# sla2216-conn-mso.net
KiCad netlist of a schematic drawn in Altium Designer
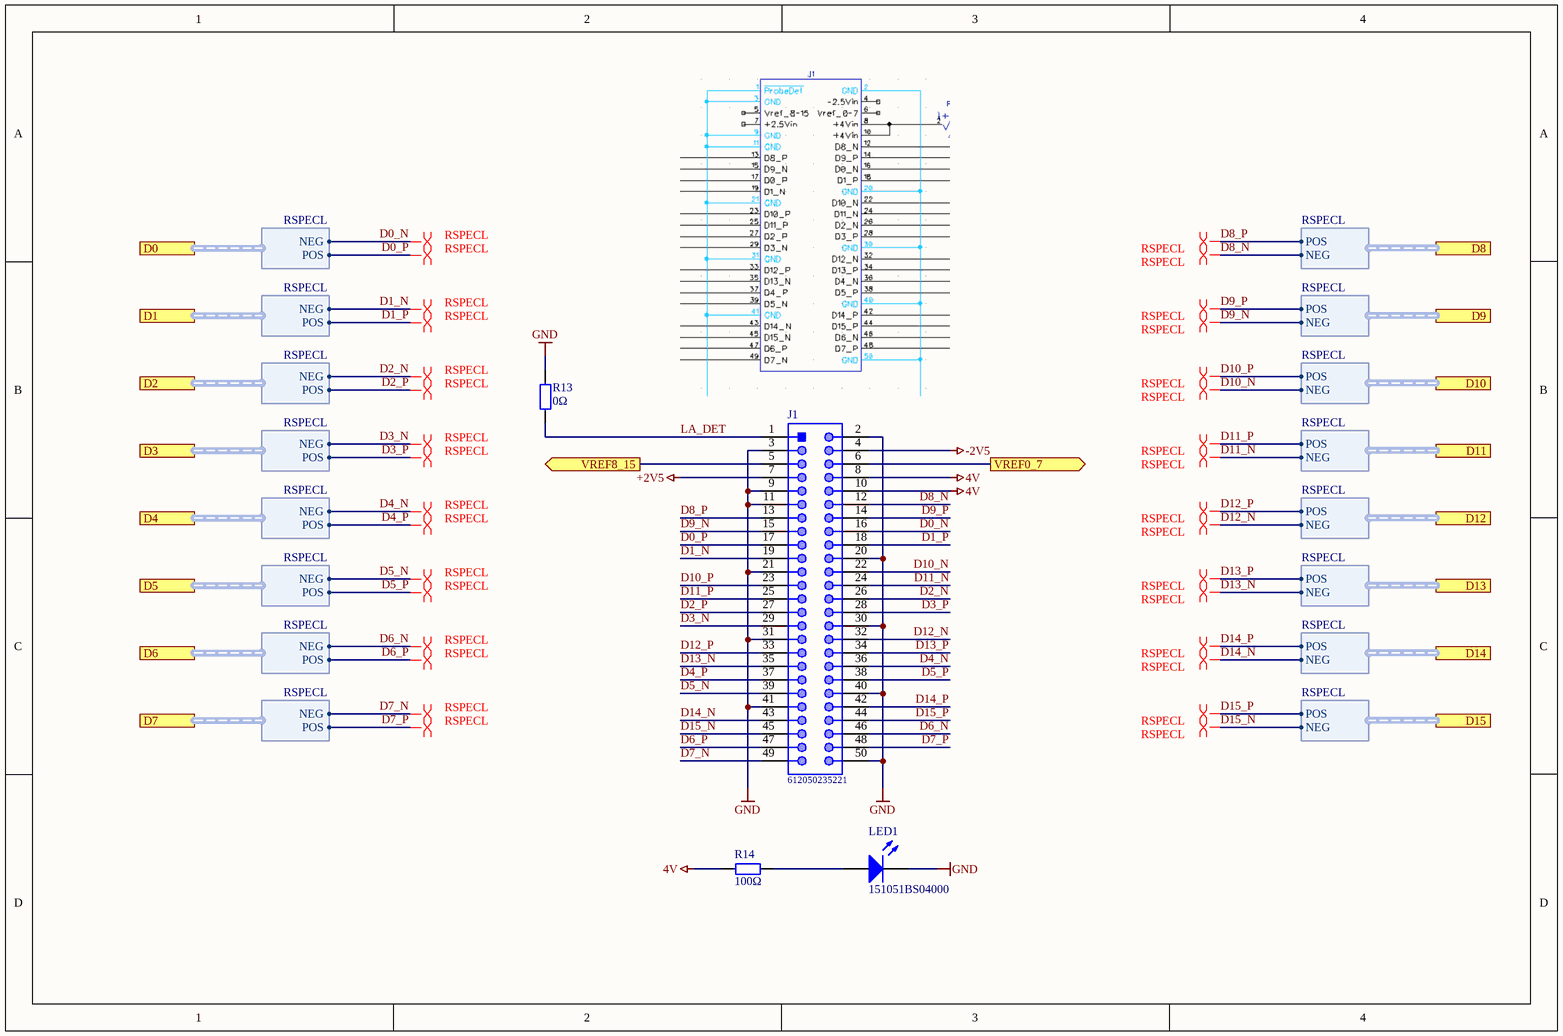
[diagram p0: sla2216-conn-mso.SchDoc]

(export (version "E")
  (design (tool "Eeschema 10.0.6"))
  (components
    (comp (ref "J1")
      (value "612050235221")
      (footprint "612050235221")
      (description "Male Box Header WR-BHD, THT, Angled, pitch 2.54 mm, 50 pins")
      (fields (field (name "MANUFACTURER") "Wurth Elektronik") (field (name "PUBLISHER") "WurthElektronik"))
      (libsource (lib "Altium Content Vault") (part "WE-CN-2P-M-R50"))
    )
    (comp (ref "LED1")
      (value "151051BS04000")
      (footprint "Type 5mm")
      (description "THT LED round mono-color color lens, WL-TMRW, Blue")
      (fields (field (name "MANUFACTURER") "Wuerth Elektronik"))
      (libsource (lib "Altium Content Vault") (part "WE-LED_K1A2-2"))
    )
    (comp (ref "R13")
      (value "~")
      (footprint "RES 0603/1608")
      (description "Resistor")
      (fields (field (name "TOLERANCE") "5%") (field (name "RESISTANCE") "0Ω"))
      (libsource (lib "altium_lib") (part "Resistor"))
    )
    (comp (ref "R14")
      (value "~")
      (footprint "RES 0603/1608")
      (description "Resistor")
      (fields (field (name "TOLERANCE") "5%") (field (name "RESISTANCE") "100Ω"))
      (libsource (lib "altium_lib") (part "Resistor"))
    )
  )
  (nets
    (net (code "2") (name "+2V5") (class "Default")
      (node (ref "J1") (pin "7") (pinfunction "7_7") (pintype "passive"))
    )
    (net (code "3") (name "-2V5") (class "Default")
      (node (ref "J1") (pin "4") (pinfunction "4_4") (pintype "passive"))
    )
    (net (code "4") (name "/D0_N") (class "Default")
      (node (ref "J1") (pin "16") (pinfunction "16_16") (pintype "passive"))
    )
    (net (code "5") (name "/D0_P") (class "Default")
      (node (ref "J1") (pin "17") (pinfunction "17_17") (pintype "passive"))
    )
    (net (code "6") (name "/D1_N") (class "Default")
      (node (ref "J1") (pin "19") (pinfunction "19_19") (pintype "passive"))
    )
    (net (code "7") (name "/D1_P") (class "Default")
      (node (ref "J1") (pin "18") (pinfunction "18_18") (pintype "passive"))
    )
    (net (code "8") (name "/D2_N") (class "Default")
      (node (ref "J1") (pin "26") (pinfunction "26_26") (pintype "passive"))
    )
    (net (code "9") (name "/D2_P") (class "Default")
      (node (ref "J1") (pin "27") (pinfunction "27_27") (pintype "passive"))
    )
    (net (code "10") (name "/D3_N") (class "Default")
      (node (ref "J1") (pin "29") (pinfunction "29_29") (pintype "passive"))
    )
    (net (code "11") (name "/D3_P") (class "Default")
      (node (ref "J1") (pin "28") (pinfunction "28_28") (pintype "passive"))
    )
    (net (code "12") (name "/D4_N") (class "Default")
      (node (ref "J1") (pin "36") (pinfunction "36_36") (pintype "passive"))
    )
    (net (code "13") (name "/D4_P") (class "Default")
      (node (ref "J1") (pin "37") (pinfunction "37_37") (pintype "passive"))
    )
    (net (code "14") (name "/D5_N") (class "Default")
      (node (ref "J1") (pin "39") (pinfunction "39_39") (pintype "passive"))
    )
    (net (code "15") (name "/D5_P") (class "Default")
      (node (ref "J1") (pin "38") (pinfunction "38_38") (pintype "passive"))
    )
    (net (code "16") (name "/D6_N") (class "Default")
      (node (ref "J1") (pin "46") (pinfunction "46_46") (pintype "passive"))
    )
    (net (code "17") (name "/D6_P") (class "Default")
      (node (ref "J1") (pin "47") (pinfunction "47_47") (pintype "passive"))
    )
    (net (code "18") (name "/D7_N") (class "Default")
      (node (ref "J1") (pin "49") (pinfunction "49_49") (pintype "passive"))
    )
    (net (code "19") (name "/D7_P") (class "Default")
      (node (ref "J1") (pin "48") (pinfunction "48_48") (pintype "passive"))
    )
    (net (code "20") (name "/D8_N") (class "Default")
      (node (ref "J1") (pin "12") (pinfunction "12_12") (pintype "passive"))
    )
    (net (code "21") (name "/D8_P") (class "Default")
      (node (ref "J1") (pin "13") (pinfunction "13_13") (pintype "passive"))
    )
    (net (code "22") (name "/D9_N") (class "Default")
      (node (ref "J1") (pin "15") (pinfunction "15_15") (pintype "passive"))
    )
    (net (code "23") (name "/D9_P") (class "Default")
      (node (ref "J1") (pin "14") (pinfunction "14_14") (pintype "passive"))
    )
    (net (code "24") (name "/D10_N") (class "Default")
      (node (ref "J1") (pin "22") (pinfunction "22_22") (pintype "passive"))
    )
    (net (code "25") (name "/D10_P") (class "Default")
      (node (ref "J1") (pin "23") (pinfunction "23_23") (pintype "passive"))
    )
    (net (code "26") (name "/D11_N") (class "Default")
      (node (ref "J1") (pin "24") (pinfunction "24_24") (pintype "passive"))
    )
    (net (code "27") (name "/D11_P") (class "Default")
      (node (ref "J1") (pin "25") (pinfunction "25_25") (pintype "passive"))
    )
    (net (code "28") (name "/D12_N") (class "Default")
      (node (ref "J1") (pin "32") (pinfunction "32_32") (pintype "passive"))
    )
    (net (code "29") (name "/D12_P") (class "Default")
      (node (ref "J1") (pin "33") (pinfunction "33_33") (pintype "passive"))
    )
    (net (code "30") (name "/D13_N") (class "Default")
      (node (ref "J1") (pin "35") (pinfunction "35_35") (pintype "passive"))
    )
    (net (code "31") (name "/D13_P") (class "Default")
      (node (ref "J1") (pin "34") (pinfunction "34_34") (pintype "passive"))
    )
    (net (code "32") (name "/D14_N") (class "Default")
      (node (ref "J1") (pin "43") (pinfunction "43_43") (pintype "passive"))
    )
    (net (code "33") (name "/D14_P") (class "Default")
      (node (ref "J1") (pin "42") (pinfunction "42_42") (pintype "passive"))
    )
    (net (code "34") (name "/D15_N") (class "Default")
      (node (ref "J1") (pin "45") (pinfunction "45_45") (pintype "passive"))
    )
    (net (code "35") (name "/D15_P") (class "Default")
      (node (ref "J1") (pin "44") (pinfunction "44_44") (pintype "passive"))
    )
    (net (code "36") (name "/LA_DET") (class "Default")
      (node (ref "J1") (pin "1") (pinfunction "1_1") (pintype "passive"))
      (node (ref "R13") (pin "2") (pinfunction "2_2") (pintype "passive"))
    )
    (net (code "37") (name "/VREF0_7") (class "Default")
      (node (ref "J1") (pin "6") (pinfunction "6_6") (pintype "passive"))
    )
    (net (code "38") (name "/VREF8_15") (class "Default")
      (node (ref "J1") (pin "5") (pinfunction "5_5") (pintype "passive"))
    )
    (net (code "40") (name "4V") (class "Default")
      (node (ref "J1") (pin "10") (pinfunction "10_10") (pintype "passive"))
      (node (ref "J1") (pin "8") (pinfunction "8_8") (pintype "passive"))
      (node (ref "R14") (pin "2") (pinfunction "2_2") (pintype "passive"))
    )
    (net (code "41") (name "GND") (class "Default")
      (node (ref "J1") (pin "11") (pinfunction "11_11") (pintype "passive"))
      (node (ref "J1") (pin "2") (pinfunction "2_2") (pintype "passive"))
      (node (ref "J1") (pin "20") (pinfunction "20_20") (pintype "passive"))
      (node (ref "J1") (pin "21") (pinfunction "21_21") (pintype "passive"))
      (node (ref "J1") (pin "3") (pinfunction "3_3") (pintype "passive"))
      (node (ref "J1") (pin "30") (pinfunction "30_30") (pintype "passive"))
      (node (ref "J1") (pin "31") (pinfunction "31_31") (pintype "passive"))
      (node (ref "J1") (pin "40") (pinfunction "40_40") (pintype "passive"))
      (node (ref "J1") (pin "41") (pinfunction "41_41") (pintype "passive"))
      (node (ref "J1") (pin "50") (pinfunction "50_50") (pintype "passive"))
      (node (ref "J1") (pin "9") (pinfunction "9_9") (pintype "passive"))
      (node (ref "LED1") (pin "1") (pinfunction "K_1") (pintype "passive"))
      (node (ref "R13") (pin "1") (pinfunction "1_1") (pintype "passive"))
    )
    (net (code "42") (name "Net-(LED1-A)") (class "Default")
      (node (ref "LED1") (pin "2") (pinfunction "A_2") (pintype "passive"))
      (node (ref "R14") (pin "1") (pinfunction "1_1") (pintype "passive"))
    )
  )
)
